# TM16_LED.net
KiCad netlist of a schematic drawn in Altium Designer
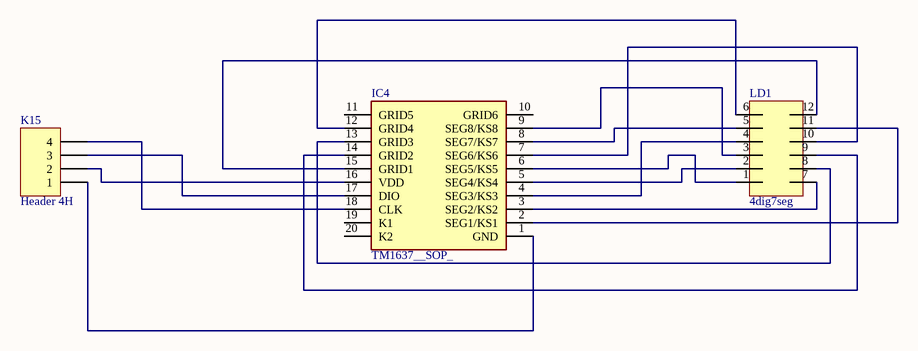
[diagram p0: TM16+LED.SchDoc]

(export (version "E")
  (design (tool "Eeschema 10.0.6"))
  (components
    (comp (ref "IC4")
      (value "TM1637__SOP_")
      (footprint "SamacSys:SOIC127P1045X280-20N")
      (description "Integrated Circuit")
      (fields (field (name "MANUFACTURER_PART_NUMBER") "TM1637 (SOP)"))
      (libsource (lib "*") (part "TM1637__SOP_"))
    )
    (comp (ref "K15")
      (value "Header 4H")
      (footprint "HDR1X4H")
      (description "Header, 4-Pin, Right Angle")
      (fields (field (name "PUBLISHER") "Altium Limited"))
      (libsource (lib "Miscellaneous Connectors") (part "Header 4H"))
    )
    (comp (ref "LD1")
      (value "4dig7seg")
      (footprint "4Digit7seg")
      (libsource (lib "Soldeerbout_12002498") (part "4dig7seg"))
    )
  )
  (nets
    (net (code "1") (name "Net-(IC4-CLK)") (class "Default")
      (node (ref "IC4") (pin "18") (pinfunction "CLK_18") (pintype "passive"))
      (node (ref "K15") (pin "4") (pinfunction "4_4") (pintype "passive"))
    )
    (net (code "2") (name "Net-(IC4-DIO)") (class "Default")
      (node (ref "IC4") (pin "17") (pinfunction "DIO_17") (pintype "passive"))
      (node (ref "K15") (pin "3") (pinfunction "3_3") (pintype "passive"))
    )
    (net (code "3") (name "Net-(IC4-GND)") (class "Default")
      (node (ref "IC4") (pin "1") (pinfunction "GND_1") (pintype "passive"))
      (node (ref "K15") (pin "1") (pinfunction "1_1") (pintype "passive"))
    )
    (net (code "4") (name "Net-(IC4-GRID1)") (class "Default")
      (node (ref "IC4") (pin "15") (pinfunction "GRID1_15") (pintype "passive"))
      (node (ref "LD1") (pin "12") (pinfunction "12_12") (pintype "passive"))
    )
    (net (code "5") (name "Net-(IC4-GRID2)") (class "Default")
      (node (ref "IC4") (pin "14") (pinfunction "GRID2_14") (pintype "passive"))
      (node (ref "LD1") (pin "9") (pinfunction "9_9") (pintype "passive"))
    )
    (net (code "6") (name "Net-(IC4-GRID3)") (class "Default")
      (node (ref "IC4") (pin "13") (pinfunction "GRID3_13") (pintype "passive"))
      (node (ref "LD1") (pin "8") (pinfunction "8_8") (pintype "passive"))
    )
    (net (code "7") (name "Net-(IC4-GRID4)") (class "Default")
      (node (ref "IC4") (pin "12") (pinfunction "GRID4_12") (pintype "passive"))
      (node (ref "LD1") (pin "6") (pinfunction "6_6") (pintype "passive"))
    )
    (net (code "8") (name "Net-(IC4-SEG1{slash}KS1)") (class "Default")
      (node (ref "IC4") (pin "2") (pinfunction "SEG1/KS1_2") (pintype "passive"))
      (node (ref "LD1") (pin "11") (pinfunction "11_11") (pintype "passive"))
    )
    (net (code "9") (name "Net-(IC4-SEG2{slash}KS2)") (class "Default")
      (node (ref "IC4") (pin "3") (pinfunction "SEG2/KS2_3") (pintype "passive"))
      (node (ref "LD1") (pin "7") (pinfunction "7_7") (pintype "passive"))
    )
    (net (code "10") (name "Net-(IC4-SEG3{slash}KS3)") (class "Default")
      (node (ref "IC4") (pin "4") (pinfunction "SEG3/KS3_4") (pintype "passive"))
      (node (ref "LD1") (pin "4") (pinfunction "4_4") (pintype "passive"))
    )
    (net (code "11") (name "Net-(IC4-SEG4{slash}KS4)") (class "Default")
      (node (ref "IC4") (pin "5") (pinfunction "SEG4/KS4_5") (pintype "passive"))
      (node (ref "LD1") (pin "2") (pinfunction "2_2") (pintype "passive"))
    )
    (net (code "12") (name "Net-(IC4-SEG5{slash}KS5)") (class "Default")
      (node (ref "IC4") (pin "6") (pinfunction "SEG5/KS5_6") (pintype "passive"))
      (node (ref "LD1") (pin "1") (pinfunction "1_1") (pintype "passive"))
    )
    (net (code "13") (name "Net-(IC4-SEG6{slash}KS6)") (class "Default")
      (node (ref "IC4") (pin "7") (pinfunction "SEG6/KS6_7") (pintype "passive"))
      (node (ref "LD1") (pin "10") (pinfunction "10_10") (pintype "passive"))
    )
    (net (code "14") (name "Net-(IC4-SEG7{slash}KS7)") (class "Default")
      (node (ref "IC4") (pin "8") (pinfunction "SEG7/KS7_8") (pintype "passive"))
      (node (ref "LD1") (pin "5") (pinfunction "5_5") (pintype "passive"))
    )
    (net (code "15") (name "Net-(IC4-SEG8{slash}KS8)") (class "Default")
      (node (ref "IC4") (pin "9") (pinfunction "SEG8/KS8_9") (pintype "passive"))
      (node (ref "LD1") (pin "3") (pinfunction "3_3") (pintype "passive"))
    )
    (net (code "16") (name "Net-(IC4-VDD)") (class "Default")
      (node (ref "IC4") (pin "16") (pinfunction "VDD_16") (pintype "passive"))
      (node (ref "K15") (pin "2") (pinfunction "2_2") (pintype "passive"))
    )
    (net (code "17") (name "unconnected-(IC4-GRID5-Pad11)") (class "Default")
      (node (ref "IC4") (pin "11") (pinfunction "GRID5_11") (pintype "passive"))
    )
    (net (code "18") (name "unconnected-(IC4-GRID6-Pad10)") (class "Default")
      (node (ref "IC4") (pin "10") (pinfunction "GRID6_10") (pintype "passive"))
    )
    (net (code "19") (name "unconnected-(IC4-K1-Pad19)") (class "Default")
      (node (ref "IC4") (pin "19") (pinfunction "K1_19") (pintype "passive"))
    )
    (net (code "20") (name "unconnected-(IC4-K2-Pad20)") (class "Default")
      (node (ref "IC4") (pin "20") (pinfunction "K2_20") (pintype "passive"))
    )
  )
)
